# 20_Torq.net
KiCad netlist of a schematic drawn in Altium Designer
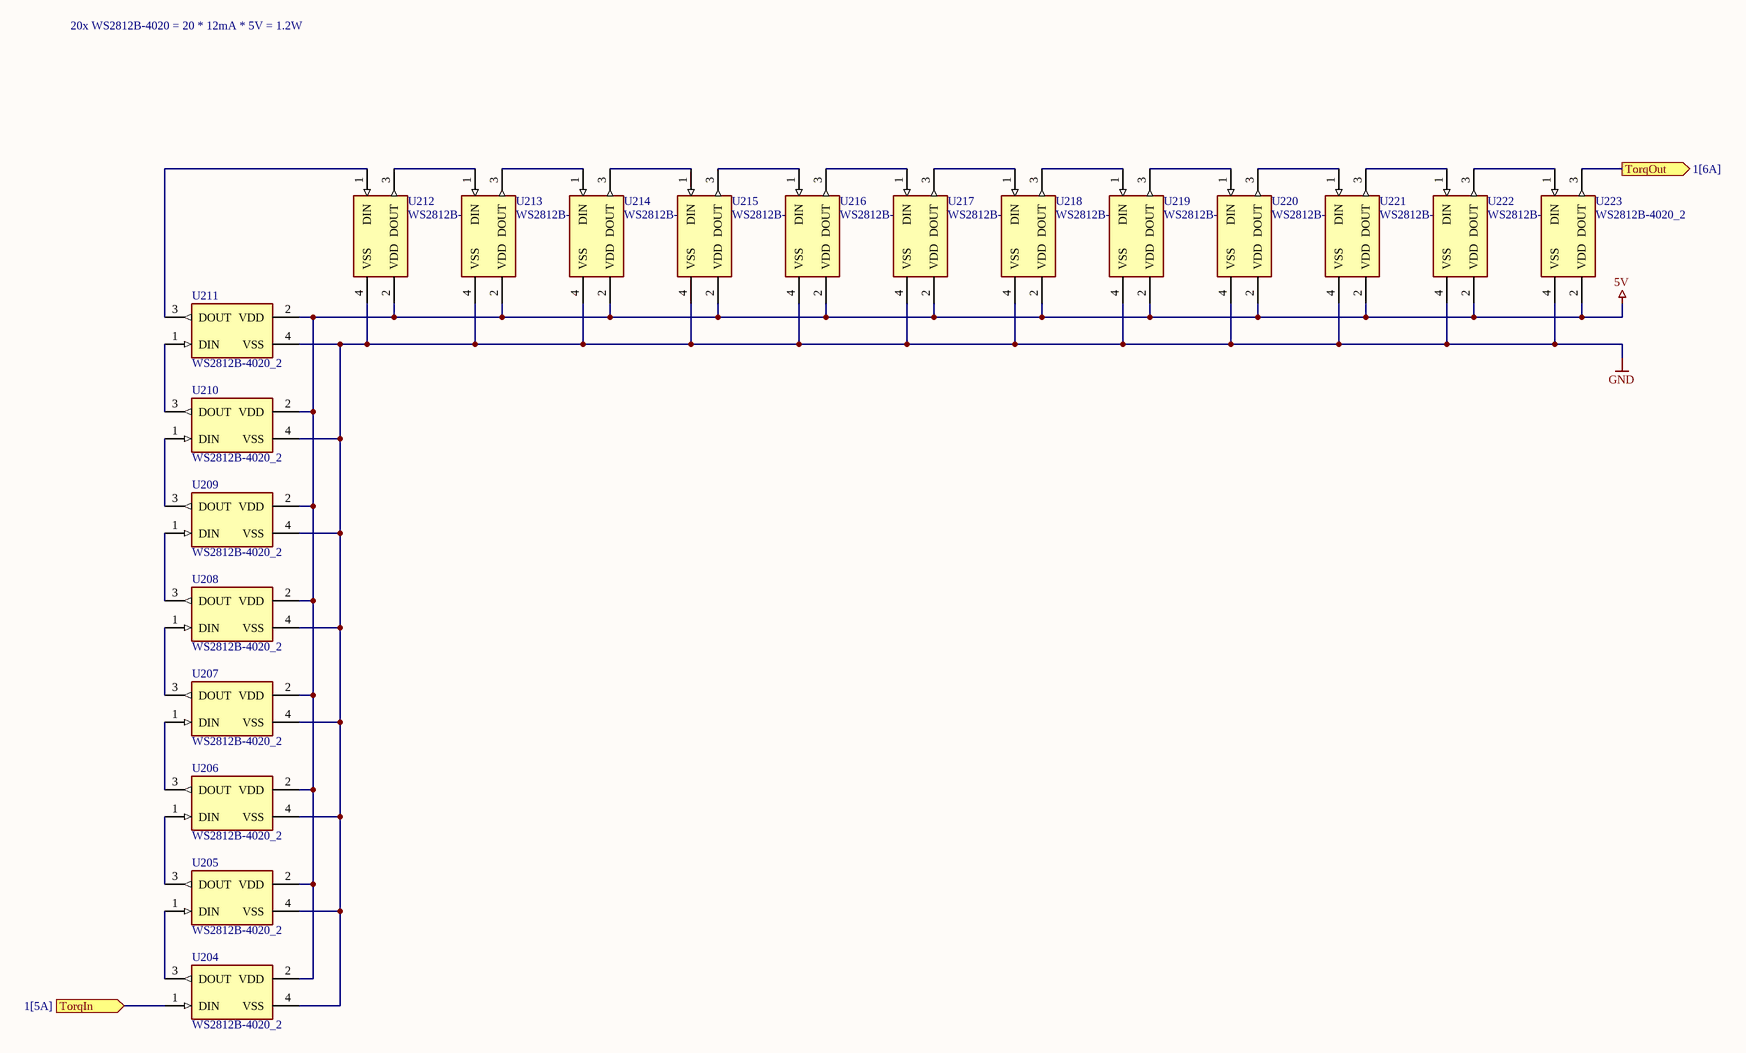
[diagram p0: 20_Torq.SchDoc]

(export (version "E")
  (design (tool "Eeschema 10.0.6"))
  (components
    (comp (ref "U204")
      (value "WS2812B-4020_2")
      (footprint "LED_WS2812B-4020")
      (description "12mA RGB SMD,2x4mm Light Emitting Diodes")
      (fields (field (name "MP") "WS2812B-4020") (field (name "MF") "Worldsemi"))
      (libsource (lib "") (part "WS2812B-4020_2_1"))
    )
    (comp (ref "U205")
      (value "WS2812B-4020_2")
      (footprint "LED_WS2812B-4020")
      (description "12mA RGB SMD,2x4mm Light Emitting Diodes")
      (fields (field (name "MP") "WS2812B-4020") (field (name "MF") "Worldsemi"))
      (libsource (lib "") (part "WS2812B-4020_2_1"))
    )
    (comp (ref "U206")
      (value "WS2812B-4020_2")
      (footprint "LED_WS2812B-4020")
      (description "12mA RGB SMD,2x4mm Light Emitting Diodes")
      (fields (field (name "MP") "WS2812B-4020") (field (name "MF") "Worldsemi"))
      (libsource (lib "") (part "WS2812B-4020_2_1"))
    )
    (comp (ref "U207")
      (value "WS2812B-4020_2")
      (footprint "LED_WS2812B-4020")
      (description "12mA RGB SMD,2x4mm Light Emitting Diodes")
      (fields (field (name "MP") "WS2812B-4020") (field (name "MF") "Worldsemi"))
      (libsource (lib "") (part "WS2812B-4020_2_1"))
    )
    (comp (ref "U208")
      (value "WS2812B-4020_2")
      (footprint "LED_WS2812B-4020")
      (description "12mA RGB SMD,2x4mm Light Emitting Diodes")
      (fields (field (name "MP") "WS2812B-4020") (field (name "MF") "Worldsemi"))
      (libsource (lib "") (part "WS2812B-4020_2_1"))
    )
    (comp (ref "U209")
      (value "WS2812B-4020_2")
      (footprint "LED_WS2812B-4020")
      (description "12mA RGB SMD,2x4mm Light Emitting Diodes")
      (fields (field (name "MP") "WS2812B-4020") (field (name "MF") "Worldsemi"))
      (libsource (lib "") (part "WS2812B-4020_2_1"))
    )
    (comp (ref "U210")
      (value "WS2812B-4020_2")
      (footprint "LED_WS2812B-4020")
      (description "12mA RGB SMD,2x4mm Light Emitting Diodes")
      (fields (field (name "MP") "WS2812B-4020") (field (name "MF") "Worldsemi"))
      (libsource (lib "") (part "WS2812B-4020_2_1"))
    )
    (comp (ref "U211")
      (value "WS2812B-4020_2")
      (footprint "LED_WS2812B-4020")
      (description "12mA RGB SMD,2x4mm Light Emitting Diodes")
      (fields (field (name "MP") "WS2812B-4020") (field (name "MF") "Worldsemi"))
      (libsource (lib "") (part "WS2812B-4020_2_1"))
    )
    (comp (ref "U212")
      (value "WS2812B-4020_2")
      (footprint "LED_WS2812B-4020")
      (description "12mA RGB SMD,2x4mm Light Emitting Diodes")
      (fields (field (name "MP") "WS2812B-4020") (field (name "MF") "Worldsemi"))
      (libsource (lib "AltiumLib_MILUTIN") (part "WS2812B-4020_2"))
    )
    (comp (ref "U213")
      (value "WS2812B-4020_2")
      (footprint "LED_WS2812B-4020")
      (description "12mA RGB SMD,2x4mm Light Emitting Diodes")
      (fields (field (name "MP") "WS2812B-4020") (field (name "MF") "Worldsemi"))
      (libsource (lib "AltiumLib_MILUTIN") (part "WS2812B-4020_2"))
    )
    (comp (ref "U214")
      (value "WS2812B-4020_2")
      (footprint "LED_WS2812B-4020")
      (description "12mA RGB SMD,2x4mm Light Emitting Diodes")
      (fields (field (name "MP") "WS2812B-4020") (field (name "MF") "Worldsemi"))
      (libsource (lib "AltiumLib_MILUTIN") (part "WS2812B-4020_2"))
    )
    (comp (ref "U215")
      (value "WS2812B-4020_2")
      (footprint "LED_WS2812B-4020")
      (description "12mA RGB SMD,2x4mm Light Emitting Diodes")
      (fields (field (name "MP") "WS2812B-4020") (field (name "MF") "Worldsemi"))
      (libsource (lib "AltiumLib_MILUTIN") (part "WS2812B-4020_2"))
    )
    (comp (ref "U216")
      (value "WS2812B-4020_2")
      (footprint "LED_WS2812B-4020")
      (description "12mA RGB SMD,2x4mm Light Emitting Diodes")
      (fields (field (name "MP") "WS2812B-4020") (field (name "MF") "Worldsemi"))
      (libsource (lib "AltiumLib_MILUTIN") (part "WS2812B-4020_2"))
    )
    (comp (ref "U217")
      (value "WS2812B-4020_2")
      (footprint "LED_WS2812B-4020")
      (description "12mA RGB SMD,2x4mm Light Emitting Diodes")
      (fields (field (name "MP") "WS2812B-4020") (field (name "MF") "Worldsemi"))
      (libsource (lib "AltiumLib_MILUTIN") (part "WS2812B-4020_2"))
    )
    (comp (ref "U218")
      (value "WS2812B-4020_2")
      (footprint "LED_WS2812B-4020")
      (description "12mA RGB SMD,2x4mm Light Emitting Diodes")
      (fields (field (name "MP") "WS2812B-4020") (field (name "MF") "Worldsemi"))
      (libsource (lib "AltiumLib_MILUTIN") (part "WS2812B-4020_2"))
    )
    (comp (ref "U219")
      (value "WS2812B-4020_2")
      (footprint "LED_WS2812B-4020")
      (description "12mA RGB SMD,2x4mm Light Emitting Diodes")
      (fields (field (name "MP") "WS2812B-4020") (field (name "MF") "Worldsemi"))
      (libsource (lib "AltiumLib_MILUTIN") (part "WS2812B-4020_2"))
    )
    (comp (ref "U220")
      (value "WS2812B-4020_2")
      (footprint "LED_WS2812B-4020")
      (description "12mA RGB SMD,2x4mm Light Emitting Diodes")
      (fields (field (name "MP") "WS2812B-4020") (field (name "MF") "Worldsemi"))
      (libsource (lib "AltiumLib_MILUTIN") (part "WS2812B-4020_2"))
    )
    (comp (ref "U221")
      (value "WS2812B-4020_2")
      (footprint "LED_WS2812B-4020")
      (description "12mA RGB SMD,2x4mm Light Emitting Diodes")
      (fields (field (name "MP") "WS2812B-4020") (field (name "MF") "Worldsemi"))
      (libsource (lib "AltiumLib_MILUTIN") (part "WS2812B-4020_2"))
    )
    (comp (ref "U222")
      (value "WS2812B-4020_2")
      (footprint "LED_WS2812B-4020")
      (description "12mA RGB SMD,2x4mm Light Emitting Diodes")
      (fields (field (name "MP") "WS2812B-4020") (field (name "MF") "Worldsemi"))
      (libsource (lib "AltiumLib_MILUTIN") (part "WS2812B-4020_2"))
    )
    (comp (ref "U223")
      (value "WS2812B-4020_2")
      (footprint "LED_WS2812B-4020")
      (description "12mA RGB SMD,2x4mm Light Emitting Diodes")
      (fields (field (name "MP") "WS2812B-4020") (field (name "MF") "Worldsemi"))
      (libsource (lib "AltiumLib_MILUTIN") (part "WS2812B-4020_2"))
    )
  )
  (nets
    (net (code "1") (name "/TorqIn") (class "Default")
      (node (ref "U204") (pin "1") (pinfunction "DIN_1") (pintype "input"))
    )
    (net (code "2") (name "/TorqOut") (class "Default")
      (node (ref "U223") (pin "3") (pinfunction "DOUT_3") (pintype "output"))
    )
    (net (code "3") (name "5V") (class "Default")
      (node (ref "U204") (pin "2") (pinfunction "VDD_2") (pintype "power_in"))
      (node (ref "U205") (pin "2") (pinfunction "VDD_2") (pintype "power_in"))
      (node (ref "U206") (pin "2") (pinfunction "VDD_2") (pintype "power_in"))
      (node (ref "U207") (pin "2") (pinfunction "VDD_2") (pintype "power_in"))
      (node (ref "U208") (pin "2") (pinfunction "VDD_2") (pintype "power_in"))
      (node (ref "U209") (pin "2") (pinfunction "VDD_2") (pintype "power_in"))
      (node (ref "U210") (pin "2") (pinfunction "VDD_2") (pintype "power_in"))
      (node (ref "U211") (pin "2") (pinfunction "VDD_2") (pintype "power_in"))
      (node (ref "U212") (pin "2") (pinfunction "VDD_2") (pintype "power_in"))
      (node (ref "U213") (pin "2") (pinfunction "VDD_2") (pintype "power_in"))
      (node (ref "U214") (pin "2") (pinfunction "VDD_2") (pintype "power_in"))
      (node (ref "U215") (pin "2") (pinfunction "VDD_2") (pintype "power_in"))
      (node (ref "U216") (pin "2") (pinfunction "VDD_2") (pintype "power_in"))
      (node (ref "U217") (pin "2") (pinfunction "VDD_2") (pintype "power_in"))
      (node (ref "U218") (pin "2") (pinfunction "VDD_2") (pintype "power_in"))
      (node (ref "U219") (pin "2") (pinfunction "VDD_2") (pintype "power_in"))
      (node (ref "U220") (pin "2") (pinfunction "VDD_2") (pintype "power_in"))
      (node (ref "U221") (pin "2") (pinfunction "VDD_2") (pintype "power_in"))
      (node (ref "U222") (pin "2") (pinfunction "VDD_2") (pintype "power_in"))
      (node (ref "U223") (pin "2") (pinfunction "VDD_2") (pintype "power_in"))
    )
    (net (code "4") (name "GND") (class "Default")
      (node (ref "U204") (pin "4") (pinfunction "VSS_4") (pintype "power_in"))
      (node (ref "U205") (pin "4") (pinfunction "VSS_4") (pintype "power_in"))
      (node (ref "U206") (pin "4") (pinfunction "VSS_4") (pintype "power_in"))
      (node (ref "U207") (pin "4") (pinfunction "VSS_4") (pintype "power_in"))
      (node (ref "U208") (pin "4") (pinfunction "VSS_4") (pintype "power_in"))
      (node (ref "U209") (pin "4") (pinfunction "VSS_4") (pintype "power_in"))
      (node (ref "U210") (pin "4") (pinfunction "VSS_4") (pintype "power_in"))
      (node (ref "U211") (pin "4") (pinfunction "VSS_4") (pintype "power_in"))
      (node (ref "U212") (pin "4") (pinfunction "VSS_4") (pintype "power_in"))
      (node (ref "U213") (pin "4") (pinfunction "VSS_4") (pintype "power_in"))
      (node (ref "U214") (pin "4") (pinfunction "VSS_4") (pintype "power_in"))
      (node (ref "U215") (pin "4") (pinfunction "VSS_4") (pintype "power_in"))
      (node (ref "U216") (pin "4") (pinfunction "VSS_4") (pintype "power_in"))
      (node (ref "U217") (pin "4") (pinfunction "VSS_4") (pintype "power_in"))
      (node (ref "U218") (pin "4") (pinfunction "VSS_4") (pintype "power_in"))
      (node (ref "U219") (pin "4") (pinfunction "VSS_4") (pintype "power_in"))
      (node (ref "U220") (pin "4") (pinfunction "VSS_4") (pintype "power_in"))
      (node (ref "U221") (pin "4") (pinfunction "VSS_4") (pintype "power_in"))
      (node (ref "U222") (pin "4") (pinfunction "VSS_4") (pintype "power_in"))
      (node (ref "U223") (pin "4") (pinfunction "VSS_4") (pintype "power_in"))
    )
    (net (code "5") (name "Net-(U204-DOUT)") (class "Default")
      (node (ref "U204") (pin "3") (pinfunction "DOUT_3") (pintype "output"))
      (node (ref "U205") (pin "1") (pinfunction "DIN_1") (pintype "input"))
    )
    (net (code "6") (name "Net-(U205-DOUT)") (class "Default")
      (node (ref "U205") (pin "3") (pinfunction "DOUT_3") (pintype "output"))
      (node (ref "U206") (pin "1") (pinfunction "DIN_1") (pintype "input"))
    )
    (net (code "7") (name "Net-(U206-DOUT)") (class "Default")
      (node (ref "U206") (pin "3") (pinfunction "DOUT_3") (pintype "output"))
      (node (ref "U207") (pin "1") (pinfunction "DIN_1") (pintype "input"))
    )
    (net (code "8") (name "Net-(U207-DOUT)") (class "Default")
      (node (ref "U207") (pin "3") (pinfunction "DOUT_3") (pintype "output"))
      (node (ref "U208") (pin "1") (pinfunction "DIN_1") (pintype "input"))
    )
    (net (code "9") (name "Net-(U208-DOUT)") (class "Default")
      (node (ref "U208") (pin "3") (pinfunction "DOUT_3") (pintype "output"))
      (node (ref "U209") (pin "1") (pinfunction "DIN_1") (pintype "input"))
    )
    (net (code "10") (name "Net-(U209-DOUT)") (class "Default")
      (node (ref "U209") (pin "3") (pinfunction "DOUT_3") (pintype "output"))
      (node (ref "U210") (pin "1") (pinfunction "DIN_1") (pintype "input"))
    )
    (net (code "11") (name "Net-(U210-DOUT)") (class "Default")
      (node (ref "U210") (pin "3") (pinfunction "DOUT_3") (pintype "output"))
      (node (ref "U211") (pin "1") (pinfunction "DIN_1") (pintype "input"))
    )
    (net (code "12") (name "Net-(U211-DOUT)") (class "Default")
      (node (ref "U211") (pin "3") (pinfunction "DOUT_3") (pintype "output"))
      (node (ref "U212") (pin "1") (pinfunction "DIN_1") (pintype "input"))
    )
    (net (code "13") (name "Net-(U212-DOUT)") (class "Default")
      (node (ref "U212") (pin "3") (pinfunction "DOUT_3") (pintype "output"))
      (node (ref "U213") (pin "1") (pinfunction "DIN_1") (pintype "input"))
    )
    (net (code "14") (name "Net-(U213-DOUT)") (class "Default")
      (node (ref "U213") (pin "3") (pinfunction "DOUT_3") (pintype "output"))
      (node (ref "U214") (pin "1") (pinfunction "DIN_1") (pintype "input"))
    )
    (net (code "15") (name "Net-(U214-DOUT)") (class "Default")
      (node (ref "U214") (pin "3") (pinfunction "DOUT_3") (pintype "output"))
      (node (ref "U215") (pin "1") (pinfunction "DIN_1") (pintype "input"))
    )
    (net (code "16") (name "Net-(U215-DOUT)") (class "Default")
      (node (ref "U215") (pin "3") (pinfunction "DOUT_3") (pintype "output"))
      (node (ref "U216") (pin "1") (pinfunction "DIN_1") (pintype "input"))
    )
    (net (code "17") (name "Net-(U216-DOUT)") (class "Default")
      (node (ref "U216") (pin "3") (pinfunction "DOUT_3") (pintype "output"))
      (node (ref "U217") (pin "1") (pinfunction "DIN_1") (pintype "input"))
    )
    (net (code "18") (name "Net-(U217-DOUT)") (class "Default")
      (node (ref "U217") (pin "3") (pinfunction "DOUT_3") (pintype "output"))
      (node (ref "U218") (pin "1") (pinfunction "DIN_1") (pintype "input"))
    )
    (net (code "19") (name "Net-(U218-DOUT)") (class "Default")
      (node (ref "U218") (pin "3") (pinfunction "DOUT_3") (pintype "output"))
      (node (ref "U219") (pin "1") (pinfunction "DIN_1") (pintype "input"))
    )
    (net (code "20") (name "Net-(U219-DOUT)") (class "Default")
      (node (ref "U219") (pin "3") (pinfunction "DOUT_3") (pintype "output"))
      (node (ref "U220") (pin "1") (pinfunction "DIN_1") (pintype "input"))
    )
    (net (code "21") (name "Net-(U220-DOUT)") (class "Default")
      (node (ref "U220") (pin "3") (pinfunction "DOUT_3") (pintype "output"))
      (node (ref "U221") (pin "1") (pinfunction "DIN_1") (pintype "input"))
    )
    (net (code "22") (name "Net-(U221-DOUT)") (class "Default")
      (node (ref "U221") (pin "3") (pinfunction "DOUT_3") (pintype "output"))
      (node (ref "U222") (pin "1") (pinfunction "DIN_1") (pintype "input"))
    )
    (net (code "23") (name "Net-(U222-DOUT)") (class "Default")
      (node (ref "U222") (pin "3") (pinfunction "DOUT_3") (pintype "output"))
      (node (ref "U223") (pin "1") (pinfunction "DIN_1") (pintype "input"))
    )
  )
)
